# GTM_BallGrippersFototransistorsConnector.net
KiCad netlist of a schematic drawn in Altium Designer
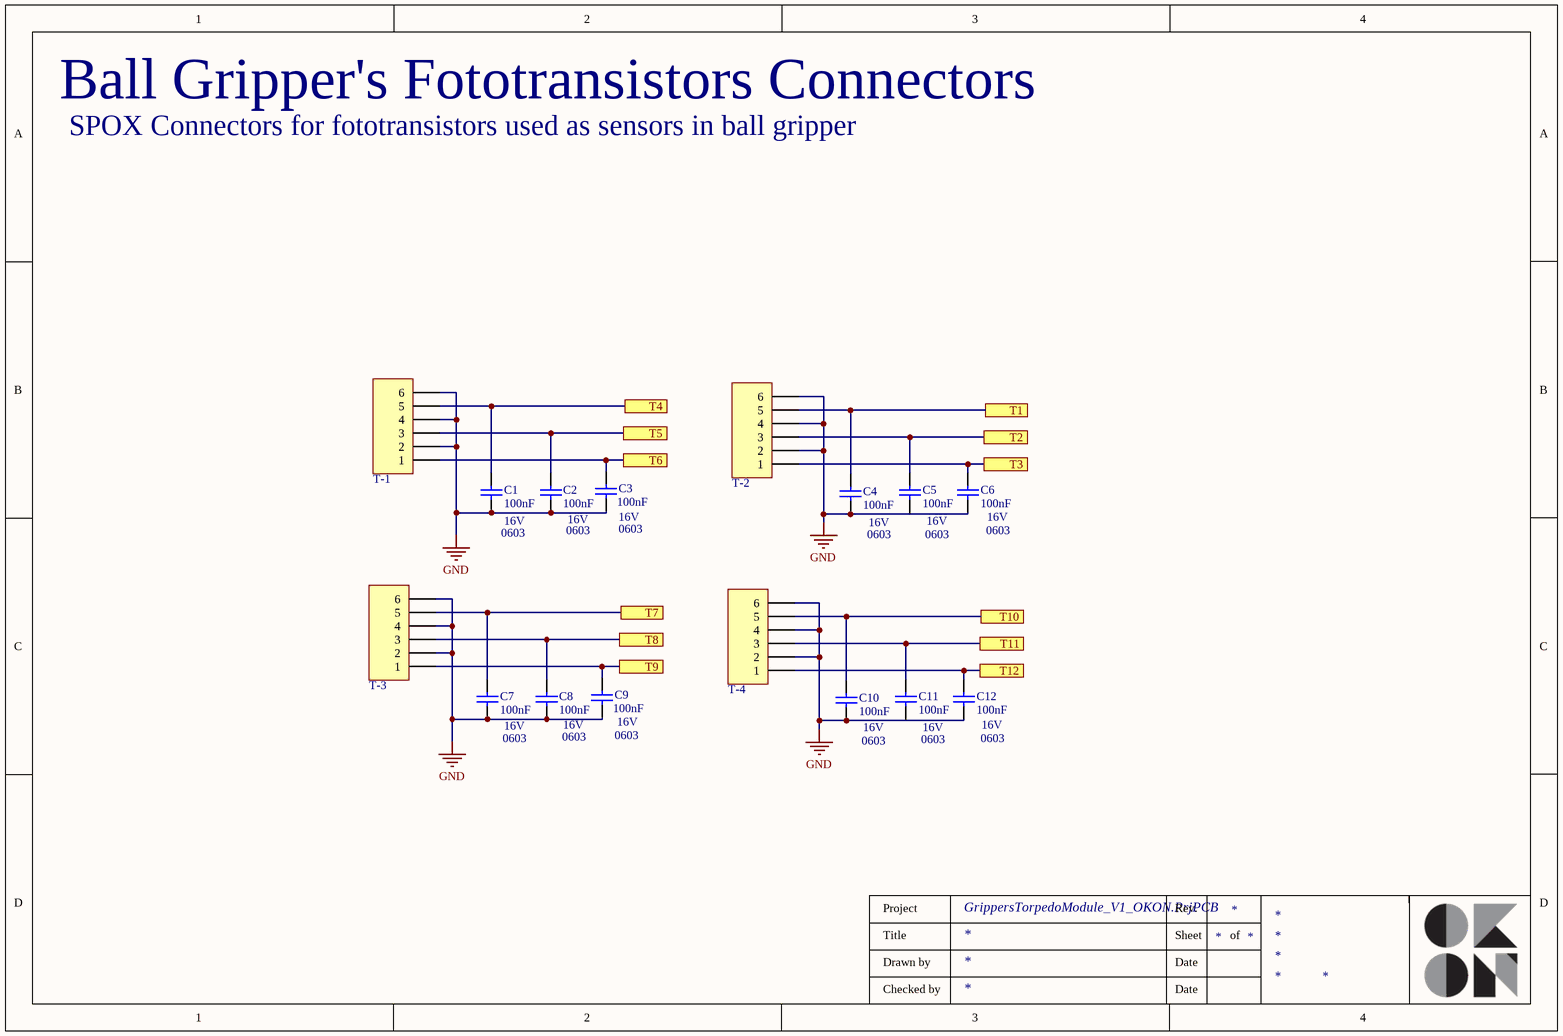
[diagram p0: GTM_BallGrippersFototransistorsConnectors.SchDoc]

(export (version "E")
  (design (tool "Eeschema 10.0.6"))
  (components
    (comp (ref "C1")
      (value "100nF")
      (footprint "0603_CAP")
      (description "Ceramic capacitor")
      (fields (field (name "PACKAGE") "0603") (field (name "CAPACITY") "16V") (field (name "Comment") "Cap"))
      (libsource (lib "Library_Altium_KNR") (part "Cap"))
    )
    (comp (ref "C2")
      (value "100nF")
      (footprint "0603_CAP")
      (description "Ceramic capacitor")
      (fields (field (name "PACKAGE") "0603") (field (name "CAPACITY") "16V") (field (name "Comment") "Cap"))
      (libsource (lib "Library_Altium_KNR") (part "Cap"))
    )
    (comp (ref "C3")
      (value "100nF")
      (footprint "0603_CAP")
      (description "Ceramic capacitor")
      (fields (field (name "PACKAGE") "0603") (field (name "CAPACITY") "16V") (field (name "Comment") "Cap"))
      (libsource (lib "Library_Altium_KNR") (part "Cap"))
    )
    (comp (ref "C4")
      (value "100nF")
      (footprint "0603_CAP")
      (description "Ceramic capacitor")
      (fields (field (name "PACKAGE") "0603") (field (name "CAPACITY") "16V") (field (name "Comment") "Cap"))
      (libsource (lib "Library_Altium_KNR") (part "Cap"))
    )
    (comp (ref "C5")
      (value "100nF")
      (footprint "0603_CAP")
      (description "Ceramic capacitor")
      (fields (field (name "PACKAGE") "0603") (field (name "CAPACITY") "16V") (field (name "Comment") "Cap"))
      (libsource (lib "Library_Altium_KNR") (part "Cap"))
    )
    (comp (ref "C6")
      (value "100nF")
      (footprint "0603_CAP")
      (description "Ceramic capacitor")
      (fields (field (name "PACKAGE") "0603") (field (name "CAPACITY") "16V") (field (name "Comment") "Cap"))
      (libsource (lib "Library_Altium_KNR") (part "Cap"))
    )
    (comp (ref "C7")
      (value "100nF")
      (footprint "0603_CAP")
      (description "Ceramic capacitor")
      (fields (field (name "PACKAGE") "0603") (field (name "CAPACITY") "16V") (field (name "Comment") "Cap"))
      (libsource (lib "Library_Altium_KNR") (part "Cap"))
    )
    (comp (ref "C8")
      (value "100nF")
      (footprint "0603_CAP")
      (description "Ceramic capacitor")
      (fields (field (name "PACKAGE") "0603") (field (name "CAPACITY") "16V") (field (name "Comment") "Cap"))
      (libsource (lib "Library_Altium_KNR") (part "Cap"))
    )
    (comp (ref "C9")
      (value "100nF")
      (footprint "0603_CAP")
      (description "Ceramic capacitor")
      (fields (field (name "PACKAGE") "0603") (field (name "CAPACITY") "16V") (field (name "Comment") "Cap"))
      (libsource (lib "Library_Altium_KNR") (part "Cap"))
    )
    (comp (ref "C10")
      (value "100nF")
      (footprint "0603_CAP")
      (description "Ceramic capacitor")
      (fields (field (name "PACKAGE") "0603") (field (name "CAPACITY") "16V") (field (name "Comment") "Cap"))
      (libsource (lib "Library_Altium_KNR") (part "Cap"))
    )
    (comp (ref "C11")
      (value "100nF")
      (footprint "0603_CAP")
      (description "Ceramic capacitor")
      (fields (field (name "PACKAGE") "0603") (field (name "CAPACITY") "16V") (field (name "Comment") "Cap"))
      (libsource (lib "Library_Altium_KNR") (part "Cap"))
    )
    (comp (ref "C12")
      (value "100nF")
      (footprint "0603_CAP")
      (description "Ceramic capacitor")
      (fields (field (name "PACKAGE") "0603") (field (name "CAPACITY") "16V") (field (name "Comment") "Cap"))
      (libsource (lib "Library_Altium_KNR") (part "Cap"))
    )
    (comp (ref "T-1")
      (value "HDR1X6")
      (footprint "Molex SPOX Horizontal 6 Circuits")
      (description "Header, 6-Pin")
      (fields (field (name "PUBLISHER") "Altium Limited"))
      (libsource (lib "Library_Altium_KNR") (part "HDR1X6"))
    )
    (comp (ref "T-2")
      (value "HDR1X6")
      (footprint "Molex SPOX Horizontal 6 Circuits")
      (description "Header, 6-Pin")
      (fields (field (name "PUBLISHER") "Altium Limited"))
      (libsource (lib "Library_Altium_KNR") (part "HDR1X6"))
    )
    (comp (ref "T-3")
      (value "HDR1X6")
      (footprint "Molex SPOX Horizontal 6 Circuits")
      (description "Header, 6-Pin")
      (fields (field (name "PUBLISHER") "Altium Limited"))
      (libsource (lib "Library_Altium_KNR") (part "HDR1X6"))
    )
    (comp (ref "T-4")
      (value "HDR1X6")
      (footprint "Molex SPOX Horizontal 6 Circuits")
      (description "Header, 6-Pin")
      (fields (field (name "PUBLISHER") "Altium Limited"))
      (libsource (lib "Library_Altium_KNR") (part "HDR1X6"))
    )
  )
  (nets
    (net (code "1") (name "/T1") (class "Default")
      (node (ref "C4") (pin "2") (pinfunction "2_2") (pintype "passive"))
      (node (ref "T-2") (pin "5") (pinfunction "5_5") (pintype "passive"))
    )
    (net (code "2") (name "/T2") (class "Default")
      (node (ref "C5") (pin "2") (pinfunction "2_2") (pintype "passive"))
      (node (ref "T-2") (pin "3") (pinfunction "3_3") (pintype "passive"))
    )
    (net (code "3") (name "/T3") (class "Default")
      (node (ref "C6") (pin "2") (pinfunction "2_2") (pintype "passive"))
      (node (ref "T-2") (pin "1") (pinfunction "1_1") (pintype "passive"))
    )
    (net (code "4") (name "/T4") (class "Default")
      (node (ref "C1") (pin "2") (pinfunction "2_2") (pintype "passive"))
      (node (ref "T-1") (pin "5") (pinfunction "5_5") (pintype "passive"))
    )
    (net (code "5") (name "/T5") (class "Default")
      (node (ref "C2") (pin "2") (pinfunction "2_2") (pintype "passive"))
      (node (ref "T-1") (pin "3") (pinfunction "3_3") (pintype "passive"))
    )
    (net (code "6") (name "/T6") (class "Default")
      (node (ref "C3") (pin "2") (pinfunction "2_2") (pintype "passive"))
      (node (ref "T-1") (pin "1") (pinfunction "1_1") (pintype "passive"))
    )
    (net (code "7") (name "/T7") (class "Default")
      (node (ref "C7") (pin "2") (pinfunction "2_2") (pintype "passive"))
      (node (ref "T-3") (pin "5") (pinfunction "5_5") (pintype "passive"))
    )
    (net (code "8") (name "/T8") (class "Default")
      (node (ref "C8") (pin "2") (pinfunction "2_2") (pintype "passive"))
      (node (ref "T-3") (pin "3") (pinfunction "3_3") (pintype "passive"))
    )
    (net (code "9") (name "/T9") (class "Default")
      (node (ref "C9") (pin "2") (pinfunction "2_2") (pintype "passive"))
      (node (ref "T-3") (pin "1") (pinfunction "1_1") (pintype "passive"))
    )
    (net (code "10") (name "/T10") (class "Default")
      (node (ref "C10") (pin "2") (pinfunction "2_2") (pintype "passive"))
      (node (ref "T-4") (pin "5") (pinfunction "5_5") (pintype "passive"))
    )
    (net (code "11") (name "/T11") (class "Default")
      (node (ref "C11") (pin "2") (pinfunction "2_2") (pintype "passive"))
      (node (ref "T-4") (pin "3") (pinfunction "3_3") (pintype "passive"))
    )
    (net (code "12") (name "/T12") (class "Default")
      (node (ref "C12") (pin "2") (pinfunction "2_2") (pintype "passive"))
      (node (ref "T-4") (pin "1") (pinfunction "1_1") (pintype "passive"))
    )
    (net (code "13") (name "GND") (class "Default")
      (node (ref "C1") (pin "1") (pinfunction "1_1") (pintype "passive"))
      (node (ref "C10") (pin "1") (pinfunction "1_1") (pintype "passive"))
      (node (ref "C12") (pin "1") (pinfunction "1_1") (pintype "passive"))
      (node (ref "C2") (pin "1") (pinfunction "1_1") (pintype "passive"))
      (node (ref "C3") (pin "1") (pinfunction "1_1") (pintype "passive"))
      (node (ref "C4") (pin "1") (pinfunction "1_1") (pintype "passive"))
      (node (ref "C6") (pin "1") (pinfunction "1_1") (pintype "passive"))
      (node (ref "C7") (pin "1") (pinfunction "1_1") (pintype "passive"))
      (node (ref "C8") (pin "1") (pinfunction "1_1") (pintype "passive"))
      (node (ref "C9") (pin "1") (pinfunction "1_1") (pintype "passive"))
      (node (ref "T-1") (pin "2") (pinfunction "2_2") (pintype "passive"))
      (node (ref "T-1") (pin "4") (pinfunction "4_4") (pintype "passive"))
      (node (ref "T-1") (pin "6") (pinfunction "6_6") (pintype "passive"))
      (node (ref "T-2") (pin "2") (pinfunction "2_2") (pintype "passive"))
      (node (ref "T-2") (pin "4") (pinfunction "4_4") (pintype "passive"))
      (node (ref "T-2") (pin "6") (pinfunction "6_6") (pintype "passive"))
      (node (ref "T-3") (pin "2") (pinfunction "2_2") (pintype "passive"))
      (node (ref "T-3") (pin "4") (pinfunction "4_4") (pintype "passive"))
      (node (ref "T-3") (pin "6") (pinfunction "6_6") (pintype "passive"))
      (node (ref "T-4") (pin "2") (pinfunction "2_2") (pintype "passive"))
      (node (ref "T-4") (pin "4") (pinfunction "4_4") (pintype "passive"))
      (node (ref "T-4") (pin "6") (pinfunction "6_6") (pintype "passive"))
    )
    (net (code "14") (name "unconnected-(C5-Pad1)") (class "Default")
      (node (ref "C5") (pin "1") (pinfunction "1_1") (pintype "passive"))
    )
    (net (code "15") (name "unconnected-(C11-Pad1)") (class "Default")
      (node (ref "C11") (pin "1") (pinfunction "1_1") (pintype "passive"))
    )
  )
)
